# dcdc.net
KiCad netlist of a schematic drawn in EAGLE
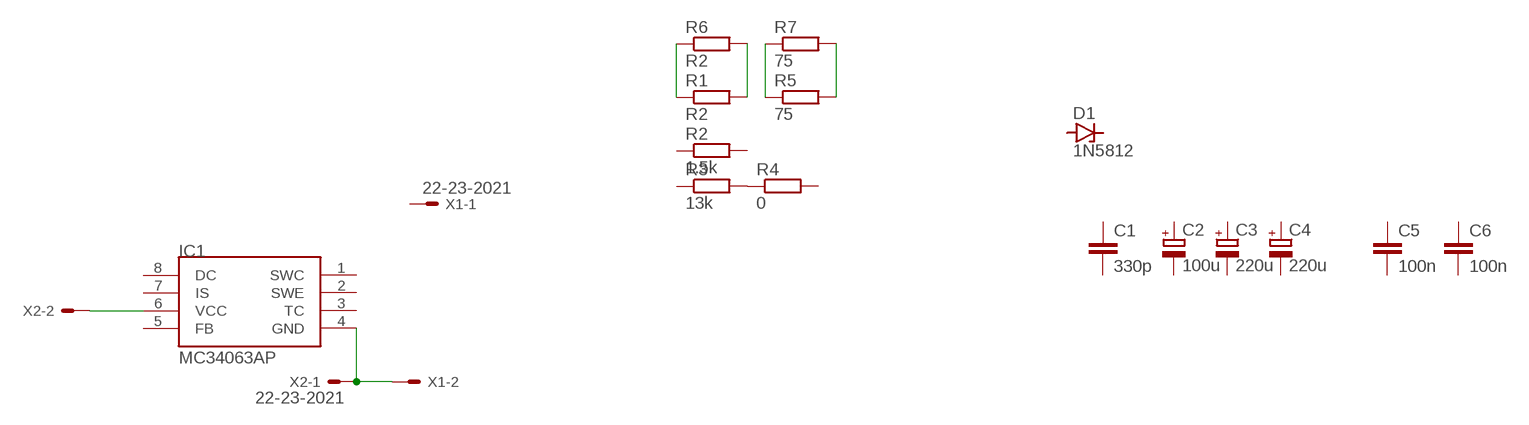
[diagram p0: schematic, sheet 1]

(export (version "E")
  (design (tool "Eeschema 10.0.6"))
  (components
    (comp (ref "C1")
      (value "330p")
      (footprint "eagle-import:C0805")
      (libsource (lib "eagle-import") (part "C-EUC0805"))
    )
    (comp (ref "C2")
      (value "100u")
      (footprint "eagle-import:E5-10,5")
      (libsource (lib "eagle-import") (part "CPOL-EUE5-10.5"))
    )
    (comp (ref "C3")
      (value "220u")
      (footprint "eagle-import:E5-10,5")
      (libsource (lib "eagle-import") (part "CPOL-EUE5-10.5"))
    )
    (comp (ref "C4")
      (value "220u")
      (footprint "eagle-import:E5-10,5")
      (libsource (lib "eagle-import") (part "CPOL-EUE5-10.5"))
    )
    (comp (ref "C5")
      (value "100n")
      (footprint "eagle-import:C0805")
      (libsource (lib "eagle-import") (part "C-EUC0805"))
    )
    (comp (ref "C6")
      (value "100n")
      (footprint "eagle-import:C0805")
      (libsource (lib "eagle-import") (part "C-EUC0805"))
    )
    (comp (ref "D1")
      (value "1N5812")
      (footprint "eagle-import:C1702-15")
      (libsource (lib "eagle-import") (part "1N5333"))
    )
    (comp (ref "IC1")
      (value "MC34063AP")
      (footprint "eagle-import:DIL08")
      (libsource (lib "eagle-import") (part "MC34063AP"))
    )
    (comp (ref "R1")
      (value "R2")
      (footprint "eagle-import:0207_10")
      (libsource (lib "eagle-import") (part "R-EU_0207/10"))
    )
    (comp (ref "R2")
      (value "1.5k")
      (footprint "eagle-import:R0805")
      (libsource (lib "eagle-import") (part "R-EU_R0805"))
    )
    (comp (ref "R3")
      (value "13k")
      (footprint "eagle-import:R0805")
      (libsource (lib "eagle-import") (part "R-EU_R0805"))
    )
    (comp (ref "R4")
      (value "0")
      (footprint "eagle-import:R0805")
      (libsource (lib "eagle-import") (part "R-EU_R0805"))
    )
    (comp (ref "R5")
      (value "75")
      (footprint "eagle-import:0207_10")
      (libsource (lib "eagle-import") (part "R-EU_0207/10"))
    )
    (comp (ref "R6")
      (value "R2")
      (footprint "eagle-import:R0805")
      (libsource (lib "eagle-import") (part "R-EU_R0805"))
    )
    (comp (ref "R7")
      (value "75")
      (footprint "eagle-import:R0805")
      (libsource (lib "eagle-import") (part "R-EU_R0805"))
    )
    (comp (ref "X1")
      (value "22-23-2021")
      (footprint "eagle-import:22-23-2021")
      (fields (field (name "MF") "MOLEX"))
      (libsource (lib "eagle-import") (part "22-23-2021"))
    )
    (comp (ref "X2")
      (value "22-23-2021")
      (footprint "eagle-import:22-23-2021")
      (fields (field (name "MF") "MOLEX"))
      (libsource (lib "eagle-import") (part "22-23-2021"))
    )
  )
  (nets
    (net (code "1") (name "Net-(IC1-GND)") (class "Default")
      (node (ref "IC1") (pin "4") (pinfunction "GND_4") (pintype "passive"))
      (node (ref "X1") (pin "2") (pinfunction "S_2") (pintype "passive"))
      (node (ref "X2") (pin "1") (pinfunction "S_1") (pintype "passive"))
    )
    (net (code "2") (name "Net-(IC1-VCC)") (class "Default")
      (node (ref "IC1") (pin "6") (pinfunction "VCC_6") (pintype "passive"))
      (node (ref "X2") (pin "2") (pinfunction "S_2") (pintype "passive"))
    )
    (net (code "3") (name "Net-(R1-Pad1)") (class "Default")
      (node (ref "R1") (pin "1") (pinfunction "1_1") (pintype "passive"))
      (node (ref "R6") (pin "1") (pinfunction "1_1") (pintype "passive"))
    )
    (net (code "4") (name "Net-(R1-Pad2)") (class "Default")
      (node (ref "R1") (pin "2") (pinfunction "2_2") (pintype "passive"))
      (node (ref "R6") (pin "2") (pinfunction "2_2") (pintype "passive"))
    )
    (net (code "5") (name "Net-(R3-Pad2)") (class "Default")
      (node (ref "R3") (pin "2") (pinfunction "2_2") (pintype "passive"))
      (node (ref "R4") (pin "1") (pinfunction "1_1") (pintype "passive"))
    )
    (net (code "6") (name "Net-(R5-Pad1)") (class "Default")
      (node (ref "R5") (pin "1") (pinfunction "1_1") (pintype "passive"))
      (node (ref "R7") (pin "1") (pinfunction "1_1") (pintype "passive"))
    )
    (net (code "7") (name "Net-(R5-Pad2)") (class "Default")
      (node (ref "R5") (pin "2") (pinfunction "2_2") (pintype "passive"))
      (node (ref "R7") (pin "2") (pinfunction "2_2") (pintype "passive"))
    )
    (net (code "8") (name "unconnected-(C1-Pad1)") (class "Default")
      (node (ref "C1") (pin "1") (pinfunction "1_1") (pintype "passive"))
    )
    (net (code "9") (name "unconnected-(C1-Pad2)") (class "Default")
      (node (ref "C1") (pin "2") (pinfunction "2_2") (pintype "passive"))
    )
    (net (code "10") (name "unconnected-(C2-Pad+)") (class "Default")
      (node (ref "C2") (pin "+") (pinfunction "+_+") (pintype "passive"))
    )
    (net (code "11") (name "unconnected-(C2-Pad-)") (class "Default")
      (node (ref "C2") (pin "-") (pinfunction "-_-") (pintype "passive"))
    )
    (net (code "12") (name "unconnected-(C3-Pad+)") (class "Default")
      (node (ref "C3") (pin "+") (pinfunction "+_+") (pintype "passive"))
    )
    (net (code "13") (name "unconnected-(C3-Pad-)") (class "Default")
      (node (ref "C3") (pin "-") (pinfunction "-_-") (pintype "passive"))
    )
    (net (code "14") (name "unconnected-(C4-Pad+)") (class "Default")
      (node (ref "C4") (pin "+") (pinfunction "+_+") (pintype "passive"))
    )
    (net (code "15") (name "unconnected-(C4-Pad-)") (class "Default")
      (node (ref "C4") (pin "-") (pinfunction "-_-") (pintype "passive"))
    )
    (net (code "16") (name "unconnected-(C5-Pad1)") (class "Default")
      (node (ref "C5") (pin "1") (pinfunction "1_1") (pintype "passive"))
    )
    (net (code "17") (name "unconnected-(C5-Pad2)") (class "Default")
      (node (ref "C5") (pin "2") (pinfunction "2_2") (pintype "passive"))
    )
    (net (code "18") (name "unconnected-(C6-Pad1)") (class "Default")
      (node (ref "C6") (pin "1") (pinfunction "1_1") (pintype "passive"))
    )
    (net (code "19") (name "unconnected-(C6-Pad2)") (class "Default")
      (node (ref "C6") (pin "2") (pinfunction "2_2") (pintype "passive"))
    )
    (net (code "20") (name "unconnected-(D1-PadA)") (class "Default")
      (node (ref "D1") (pin "A") (pinfunction "A_A") (pintype "passive"))
    )
    (net (code "21") (name "unconnected-(D1-PadC)") (class "Default")
      (node (ref "D1") (pin "C") (pinfunction "C_C") (pintype "passive"))
    )
    (net (code "22") (name "unconnected-(IC1-DC-Pad8)") (class "Default")
      (node (ref "IC1") (pin "8") (pinfunction "DC_8") (pintype "passive"))
    )
    (net (code "23") (name "unconnected-(IC1-FB-Pad5)") (class "Default")
      (node (ref "IC1") (pin "5") (pinfunction "FB_5") (pintype "passive"))
    )
    (net (code "24") (name "unconnected-(IC1-IS-Pad7)") (class "Default")
      (node (ref "IC1") (pin "7") (pinfunction "IS_7") (pintype "passive"))
    )
    (net (code "25") (name "unconnected-(IC1-SWC-Pad1)") (class "Default")
      (node (ref "IC1") (pin "1") (pinfunction "SWC_1") (pintype "passive"))
    )
    (net (code "26") (name "unconnected-(IC1-SWE-Pad2)") (class "Default")
      (node (ref "IC1") (pin "2") (pinfunction "SWE_2") (pintype "passive"))
    )
    (net (code "27") (name "unconnected-(IC1-TC-Pad3)") (class "Default")
      (node (ref "IC1") (pin "3") (pinfunction "TC_3") (pintype "passive"))
    )
    (net (code "28") (name "unconnected-(R2-Pad1)") (class "Default")
      (node (ref "R2") (pin "1") (pinfunction "1_1") (pintype "passive"))
    )
    (net (code "29") (name "unconnected-(R2-Pad2)") (class "Default")
      (node (ref "R2") (pin "2") (pinfunction "2_2") (pintype "passive"))
    )
    (net (code "30") (name "unconnected-(R3-Pad1)") (class "Default")
      (node (ref "R3") (pin "1") (pinfunction "1_1") (pintype "passive"))
    )
    (net (code "31") (name "unconnected-(R4-Pad2)") (class "Default")
      (node (ref "R4") (pin "2") (pinfunction "2_2") (pintype "passive"))
    )
    (net (code "32") (name "unconnected-(X1A-S-Pad1)") (class "Default")
      (node (ref "X1") (pin "1") (pinfunction "S_1") (pintype "passive"))
    )
  )
)
